# teemsyUp.net
KiCad netlist of a schematic drawn in EAGLE
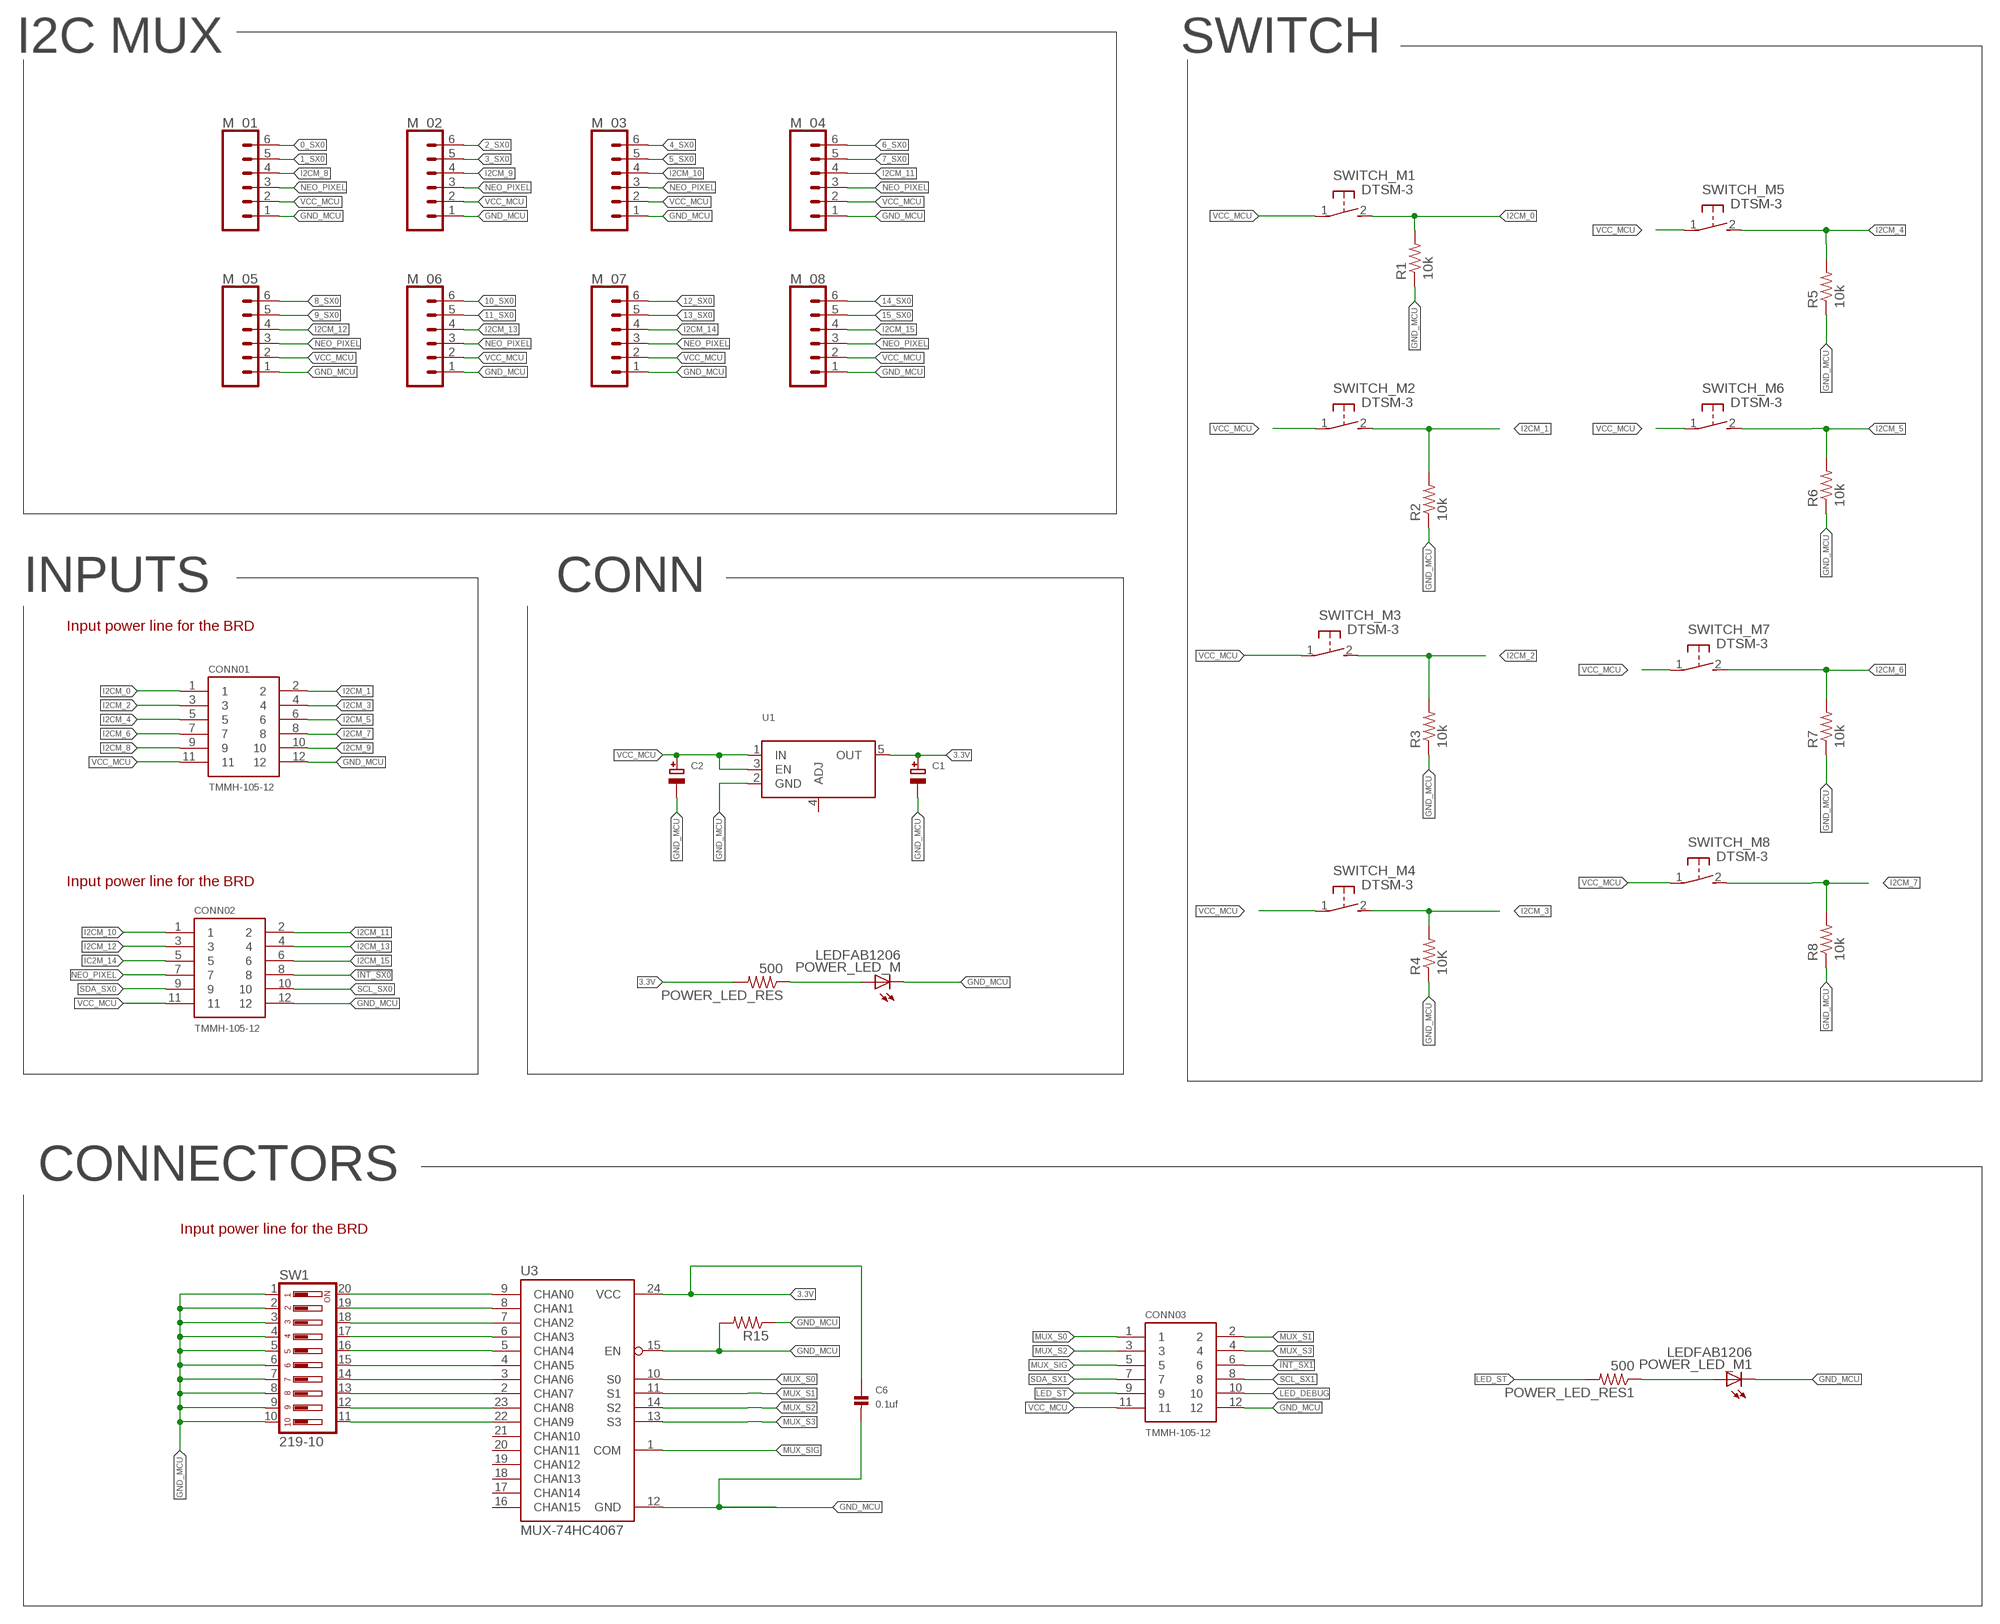
[diagram p0: schematic, sheet 1, part 1 of 2]
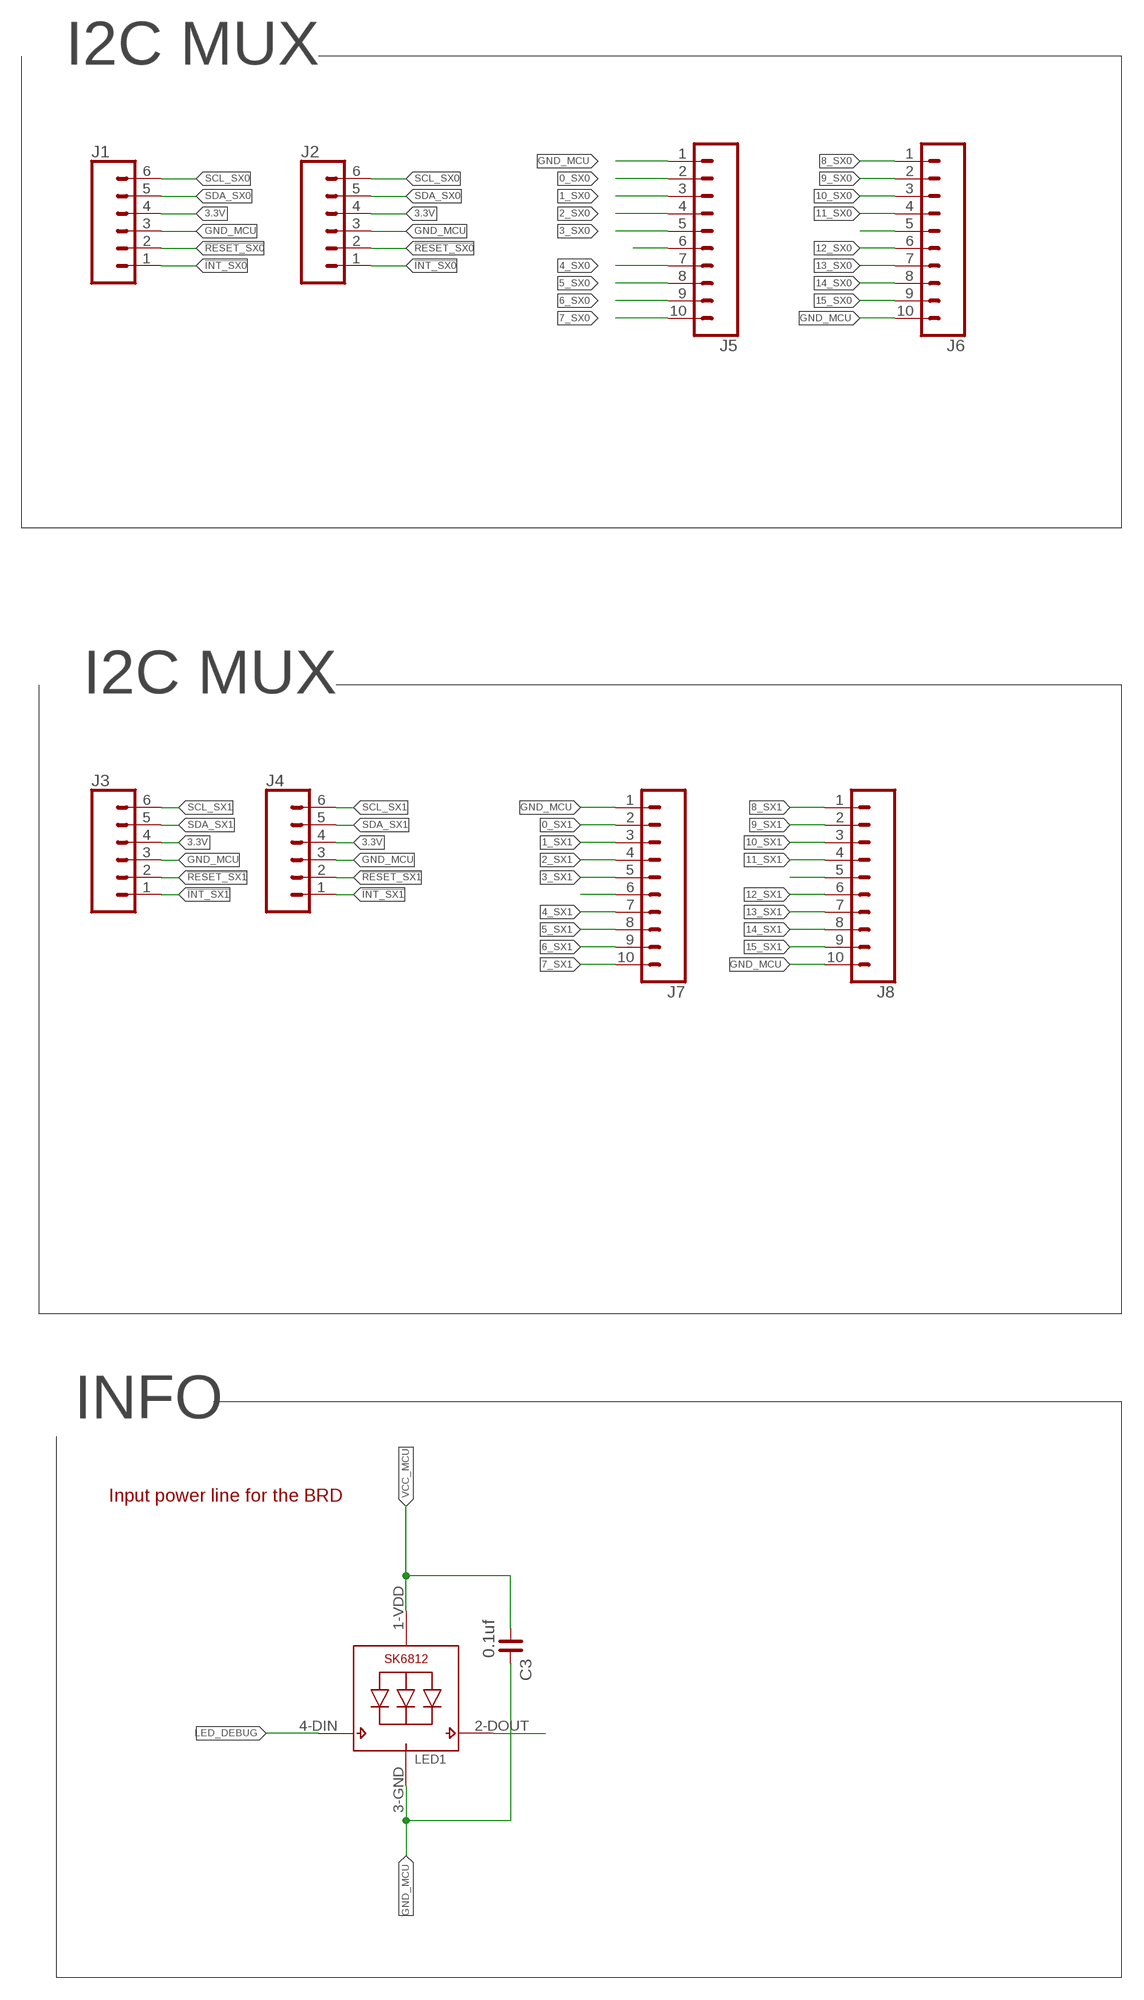
[diagram p1: schematic, sheet 1, part 2 of 2]

(export (version "E")
  (design (tool "Eeschema 10.0.6"))
  (components
    (comp (ref "C1")
      (value "CAP_TANTALUMA/3216_REFLOW")
      (footprint "eagle-import:EIA3216-18_A-R")
      (libsource (lib "eagle-import") (part "CAP_TANTALUMA/3216_REFLOW"))
    )
    (comp (ref "C2")
      (value "CAP_TANTALUMA/3216_REFLOW")
      (footprint "eagle-import:EIA3216-18_A-R")
      (libsource (lib "eagle-import") (part "CAP_TANTALUMA/3216_REFLOW"))
    )
    (comp (ref "C3")
      (value "0.1uf")
      (footprint "eagle-import:C0805")
      (libsource (lib "eagle-import") (part "C_0805"))
    )
    (comp (ref "C6")
      (value "0.1uf")
      (footprint "eagle-import:0805")
      (libsource (lib "eagle-import") (part "CAP_CERAMIC0805"))
    )
    (comp (ref "CONN01")
      (value "TMMH-105-12")
      (footprint "eagle-import:TMMH-105-12")
      (libsource (lib "eagle-import") (part "TMMH-105-12"))
    )
    (comp (ref "CONN02")
      (value "TMMH-105-12")
      (footprint "eagle-import:TMMH-105-12")
      (libsource (lib "eagle-import") (part "TMMH-105-12"))
    )
    (comp (ref "CONN03")
      (value "TMMH-105-12")
      (footprint "eagle-import:TMMH-105-12")
      (libsource (lib "eagle-import") (part "TMMH-105-12"))
    )
    (comp (ref "J1")
      (value "CONN_06SMD_MALE")
      (footprint "eagle-import:1X06_SMD_MALE")
      (libsource (lib "eagle-import") (part "CONN_06SMD_MALE"))
    )
    (comp (ref "J2")
      (value "CONN_06SMD_MALE")
      (footprint "eagle-import:1X06_SMD_MALE")
      (libsource (lib "eagle-import") (part "CONN_06SMD_MALE"))
    )
    (comp (ref "J3")
      (value "CONN_06SMD_MALE")
      (footprint "eagle-import:1X06_SMD_MALE")
      (libsource (lib "eagle-import") (part "CONN_06SMD_MALE"))
    )
    (comp (ref "J4")
      (value "CONN_06SMD_MALE")
      (footprint "eagle-import:1X06_SMD_MALE")
      (libsource (lib "eagle-import") (part "CONN_06SMD_MALE"))
    )
    (comp (ref "J5")
      (value "CONN_10SMD_MALE")
      (footprint "eagle-import:1X10_SMD_MALE")
      (libsource (lib "eagle-import") (part "CONN_10SMD_MALE"))
    )
    (comp (ref "J6")
      (value "CONN_10SMD_MALE")
      (footprint "eagle-import:1X10_SMD_MALE")
      (libsource (lib "eagle-import") (part "CONN_10SMD_MALE"))
    )
    (comp (ref "J7")
      (value "CONN_10SMD_MALE")
      (footprint "eagle-import:1X10_SMD_MALE")
      (libsource (lib "eagle-import") (part "CONN_10SMD_MALE"))
    )
    (comp (ref "J8")
      (value "CONN_10SMD_MALE")
      (footprint "eagle-import:1X10_SMD_MALE")
      (libsource (lib "eagle-import") (part "CONN_10SMD_MALE"))
    )
    (comp (ref "LED1")
      (value "SK6812_5050N")
      (footprint "eagle-import:LED5050_N")
      (libsource (lib "eagle-import") (part "SK6812_5050N"))
    )
    (comp (ref "M_01")
      (value "CONN_06SMD-1MM")
      (footprint "eagle-import:1X06-1MM")
      (libsource (lib "eagle-import") (part "CONN_06SMD-1MM"))
    )
    (comp (ref "M_02")
      (value "CONN_06SMD-1MM")
      (footprint "eagle-import:1X06-1MM")
      (libsource (lib "eagle-import") (part "CONN_06SMD-1MM"))
    )
    (comp (ref "M_03")
      (value "CONN_06SMD-1MM")
      (footprint "eagle-import:1X06-1MM")
      (libsource (lib "eagle-import") (part "CONN_06SMD-1MM"))
    )
    (comp (ref "M_04")
      (value "CONN_06SMD-1MM")
      (footprint "eagle-import:1X06-1MM")
      (libsource (lib "eagle-import") (part "CONN_06SMD-1MM"))
    )
    (comp (ref "M_05")
      (value "CONN_06SMD-1MM")
      (footprint "eagle-import:1X06-1MM")
      (libsource (lib "eagle-import") (part "CONN_06SMD-1MM"))
    )
    (comp (ref "M_06")
      (value "CONN_06SMD-1MM")
      (footprint "eagle-import:1X06-1MM")
      (libsource (lib "eagle-import") (part "CONN_06SMD-1MM"))
    )
    (comp (ref "M_07")
      (value "CONN_06SMD-1MM")
      (footprint "eagle-import:1X06-1MM")
      (libsource (lib "eagle-import") (part "CONN_06SMD-1MM"))
    )
    (comp (ref "M_08")
      (value "CONN_06SMD-1MM")
      (footprint "eagle-import:1X06-1MM")
      (libsource (lib "eagle-import") (part "CONN_06SMD-1MM"))
    )
    (comp (ref "POWER_LED_M")
      (value "LEDFAB1206")
      (footprint "eagle-import:LED1206FAB")
      (libsource (lib "eagle-import") (part "LEDFAB1206"))
    )
    (comp (ref "POWER_LED_M1")
      (value "LEDFAB1206")
      (footprint "eagle-import:LED1206FAB")
      (libsource (lib "eagle-import") (part "LEDFAB1206"))
    )
    (comp (ref "POWER_LED_RES")
      (value "500")
      (footprint "eagle-import:M0805")
      (libsource (lib "eagle-import") (part "R-US_M0805"))
    )
    (comp (ref "POWER_LED_RES1")
      (value "500")
      (footprint "eagle-import:R0805")
      (libsource (lib "eagle-import") (part "R-US_R0805"))
    )
    (comp (ref "R1")
      (value "10k")
      (footprint "eagle-import:M0805")
      (libsource (lib "eagle-import") (part "R-US_M0805"))
    )
    (comp (ref "R2")
      (value "10k")
      (footprint "eagle-import:M0805")
      (libsource (lib "eagle-import") (part "R-US_M0805"))
    )
    (comp (ref "R3")
      (value "10k")
      (footprint "eagle-import:M0805")
      (libsource (lib "eagle-import") (part "R-US_M0805"))
    )
    (comp (ref "R4")
      (value "10K")
      (footprint "eagle-import:M0805")
      (libsource (lib "eagle-import") (part "R-US_M0805"))
    )
    (comp (ref "R5")
      (value "10k")
      (footprint "eagle-import:M0805")
      (libsource (lib "eagle-import") (part "R-US_M0805"))
    )
    (comp (ref "R6")
      (value "10k")
      (footprint "eagle-import:M0805")
      (libsource (lib "eagle-import") (part "R-US_M0805"))
    )
    (comp (ref "R7")
      (value "10k")
      (footprint "eagle-import:M0805")
      (libsource (lib "eagle-import") (part "R-US_M0805"))
    )
    (comp (ref "R8")
      (value "10k")
      (footprint "eagle-import:M0805")
      (libsource (lib "eagle-import") (part "R-US_M0805"))
    )
    (comp (ref "R15")
      (value "R-US_M0805")
      (footprint "eagle-import:M0805")
      (libsource (lib "eagle-import") (part "R-US_M0805"))
    )
    (comp (ref "SW1")
      (value "219-10")
      (footprint "eagle-import:CTS-219-10")
      (fields (field (name "MF") "SLI (CML/IDI)") (field (name "MPN") "219-10PK"))
      (libsource (lib "eagle-import") (part "219-10"))
    )
    (comp (ref "SWITCH_M1")
      (value "DTSM-3")
      (footprint "eagle-import:DTSM-3")
      (libsource (lib "eagle-import") (part "DTSM-3"))
    )
    (comp (ref "SWITCH_M2")
      (value "DTSM-3")
      (footprint "eagle-import:DTSM-3")
      (libsource (lib "eagle-import") (part "DTSM-3"))
    )
    (comp (ref "SWITCH_M3")
      (value "DTSM-3")
      (footprint "eagle-import:DTSM-3")
      (libsource (lib "eagle-import") (part "DTSM-3"))
    )
    (comp (ref "SWITCH_M4")
      (value "DTSM-3")
      (footprint "eagle-import:DTSM-3")
      (libsource (lib "eagle-import") (part "DTSM-3"))
    )
    (comp (ref "SWITCH_M5")
      (value "DTSM-3")
      (footprint "eagle-import:DTSM-3")
      (libsource (lib "eagle-import") (part "DTSM-3"))
    )
    (comp (ref "SWITCH_M6")
      (value "DTSM-3")
      (footprint "eagle-import:DTSM-3")
      (libsource (lib "eagle-import") (part "DTSM-3"))
    )
    (comp (ref "SWITCH_M7")
      (value "DTSM-3")
      (footprint "eagle-import:DTSM-3")
      (libsource (lib "eagle-import") (part "DTSM-3"))
    )
    (comp (ref "SWITCH_M8")
      (value "DTSM-3")
      (footprint "eagle-import:DTSM-3")
      (libsource (lib "eagle-import") (part "DTSM-3"))
    )
    (comp (ref "U1")
      (value "ADP1712")
      (footprint "eagle-import:SOT23-5")
      (libsource (lib "eagle-import") (part "ADP1712"))
    )
    (comp (ref "U3")
      (value "MUX-74HC4067")
      (footprint "eagle-import:SSOP24")
      (libsource (lib "eagle-import") (part "MUX-74HC4067SMD"))
    )
  )
  (nets
    (net (code "1") (name "/~{INT_SX0}") (class "Default")
      (node (ref "CONN02") (pin "8") (pinfunction "8_8") (pintype "bidirectional"))
      (node (ref "J1") (pin "1") (pinfunction "1_1") (pintype "passive"))
      (node (ref "J2") (pin "1") (pinfunction "1_1") (pintype "passive"))
    )
    (net (code "2") (name "/~{INT_SX1}") (class "Default")
      (node (ref "CONN03") (pin "6") (pinfunction "6_6") (pintype "bidirectional"))
      (node (ref "J3") (pin "1") (pinfunction "1_1") (pintype "passive"))
      (node (ref "J4") (pin "1") (pinfunction "1_1") (pintype "passive"))
    )
    (net (code "3") (name "/~{RESET_SX0}") (class "Default")
      (node (ref "J1") (pin "2") (pinfunction "2_2") (pintype "passive"))
      (node (ref "J2") (pin "2") (pinfunction "2_2") (pintype "passive"))
    )
    (net (code "4") (name "/~{RESET_SX1}") (class "Default")
      (node (ref "J3") (pin "2") (pinfunction "2_2") (pintype "passive"))
      (node (ref "J4") (pin "2") (pinfunction "2_2") (pintype "passive"))
    )
    (net (code "5") (name "0_SX0") (class "Default")
      (node (ref "J5") (pin "2") (pinfunction "2_2") (pintype "passive"))
      (node (ref "M_01") (pin "6") (pinfunction "6_6") (pintype "passive"))
    )
    (net (code "6") (name "0_SX1") (class "Default")
      (node (ref "J7") (pin "2") (pinfunction "2_2") (pintype "passive"))
    )
    (net (code "7") (name "1_SX0") (class "Default")
      (node (ref "J5") (pin "3") (pinfunction "3_3") (pintype "passive"))
      (node (ref "M_01") (pin "5") (pinfunction "5_5") (pintype "passive"))
    )
    (net (code "8") (name "1_SX1") (class "Default")
      (node (ref "J7") (pin "3") (pinfunction "3_3") (pintype "passive"))
    )
    (net (code "9") (name "2_SX0") (class "Default")
      (node (ref "J5") (pin "4") (pinfunction "4_4") (pintype "passive"))
      (node (ref "M_02") (pin "6") (pinfunction "6_6") (pintype "passive"))
    )
    (net (code "10") (name "2_SX1") (class "Default")
      (node (ref "J7") (pin "4") (pinfunction "4_4") (pintype "passive"))
    )
    (net (code "11") (name "3.3V") (class "Default")
      (node (ref "C1") (pin "+") (pinfunction "+_+") (pintype "passive"))
      (node (ref "C6") (pin "1") (pinfunction "P$1_1") (pintype "passive"))
      (node (ref "J1") (pin "4") (pinfunction "4_4") (pintype "passive"))
      (node (ref "J2") (pin "4") (pinfunction "4_4") (pintype "passive"))
      (node (ref "J3") (pin "4") (pinfunction "4_4") (pintype "passive"))
      (node (ref "J4") (pin "4") (pinfunction "4_4") (pintype "passive"))
      (node (ref "POWER_LED_RES") (pin "2") (pinfunction "2_2") (pintype "passive"))
      (node (ref "U1") (pin "5") (pinfunction "OUT_5") (pintype "bidirectional"))
      (node (ref "U3") (pin "24") (pinfunction "VCC_24") (pintype "bidirectional"))
    )
    (net (code "12") (name "3_SX0") (class "Default")
      (node (ref "J5") (pin "5") (pinfunction "5_5") (pintype "passive"))
      (node (ref "M_02") (pin "5") (pinfunction "5_5") (pintype "passive"))
    )
    (net (code "13") (name "3_SX1") (class "Default")
      (node (ref "J7") (pin "5") (pinfunction "5_5") (pintype "passive"))
    )
    (net (code "14") (name "4_SX0") (class "Default")
      (node (ref "J5") (pin "7") (pinfunction "7_7") (pintype "passive"))
      (node (ref "M_03") (pin "6") (pinfunction "6_6") (pintype "passive"))
    )
    (net (code "15") (name "4_SX1") (class "Default")
      (node (ref "J7") (pin "7") (pinfunction "7_7") (pintype "passive"))
    )
    (net (code "16") (name "5_SX0") (class "Default")
      (node (ref "J5") (pin "8") (pinfunction "8_8") (pintype "passive"))
      (node (ref "M_03") (pin "5") (pinfunction "5_5") (pintype "passive"))
    )
    (net (code "17") (name "5_SX1") (class "Default")
      (node (ref "J7") (pin "8") (pinfunction "8_8") (pintype "passive"))
    )
    (net (code "18") (name "6_SX0") (class "Default")
      (node (ref "J5") (pin "9") (pinfunction "9_9") (pintype "passive"))
      (node (ref "M_04") (pin "6") (pinfunction "6_6") (pintype "passive"))
    )
    (net (code "19") (name "6_SX1") (class "Default")
      (node (ref "J7") (pin "9") (pinfunction "9_9") (pintype "passive"))
    )
    (net (code "20") (name "7_SX0") (class "Default")
      (node (ref "J5") (pin "10") (pinfunction "10_10") (pintype "passive"))
      (node (ref "M_04") (pin "5") (pinfunction "5_5") (pintype "passive"))
    )
    (net (code "21") (name "7_SX1") (class "Default")
      (node (ref "J7") (pin "10") (pinfunction "10_10") (pintype "passive"))
    )
    (net (code "22") (name "8_SX0") (class "Default")
      (node (ref "J6") (pin "1") (pinfunction "1_1") (pintype "passive"))
      (node (ref "M_05") (pin "6") (pinfunction "6_6") (pintype "passive"))
    )
    (net (code "23") (name "8_SX1") (class "Default")
      (node (ref "J8") (pin "1") (pinfunction "1_1") (pintype "passive"))
    )
    (net (code "24") (name "9_SX0") (class "Default")
      (node (ref "J6") (pin "2") (pinfunction "2_2") (pintype "passive"))
      (node (ref "M_05") (pin "5") (pinfunction "5_5") (pintype "passive"))
    )
    (net (code "25") (name "9_SX1") (class "Default")
      (node (ref "J8") (pin "2") (pinfunction "2_2") (pintype "passive"))
    )
    (net (code "26") (name "10_SX0") (class "Default")
      (node (ref "J6") (pin "3") (pinfunction "3_3") (pintype "passive"))
      (node (ref "M_06") (pin "6") (pinfunction "6_6") (pintype "passive"))
    )
    (net (code "27") (name "10_SX1") (class "Default")
      (node (ref "J8") (pin "3") (pinfunction "3_3") (pintype "passive"))
    )
    (net (code "28") (name "11_SX0") (class "Default")
      (node (ref "J6") (pin "4") (pinfunction "4_4") (pintype "passive"))
      (node (ref "M_06") (pin "5") (pinfunction "5_5") (pintype "passive"))
    )
    (net (code "29") (name "11_SX1") (class "Default")
      (node (ref "J8") (pin "4") (pinfunction "4_4") (pintype "passive"))
    )
    (net (code "30") (name "12_SX0") (class "Default")
      (node (ref "J6") (pin "6") (pinfunction "6_6") (pintype "passive"))
      (node (ref "M_07") (pin "6") (pinfunction "6_6") (pintype "passive"))
    )
    (net (code "31") (name "12_SX1") (class "Default")
      (node (ref "J8") (pin "6") (pinfunction "6_6") (pintype "passive"))
    )
    (net (code "32") (name "13_SX0") (class "Default")
      (node (ref "J6") (pin "7") (pinfunction "7_7") (pintype "passive"))
      (node (ref "M_07") (pin "5") (pinfunction "5_5") (pintype "passive"))
    )
    (net (code "33") (name "13_SX1") (class "Default")
      (node (ref "J8") (pin "7") (pinfunction "7_7") (pintype "passive"))
    )
    (net (code "34") (name "14_SX0") (class "Default")
      (node (ref "J6") (pin "8") (pinfunction "8_8") (pintype "passive"))
      (node (ref "M_08") (pin "6") (pinfunction "6_6") (pintype "passive"))
    )
    (net (code "35") (name "14_SX1") (class "Default")
      (node (ref "J8") (pin "8") (pinfunction "8_8") (pintype "passive"))
    )
    (net (code "36") (name "15_SX0") (class "Default")
      (node (ref "J6") (pin "9") (pinfunction "9_9") (pintype "passive"))
      (node (ref "M_08") (pin "5") (pinfunction "5_5") (pintype "passive"))
    )
    (net (code "37") (name "15_SX1") (class "Default")
      (node (ref "J8") (pin "9") (pinfunction "9_9") (pintype "passive"))
    )
    (net (code "38") (name "GND_MCU") (class "Default")
      (node (ref "C1") (pin "-") (pinfunction "-_-") (pintype "passive"))
      (node (ref "C2") (pin "-") (pinfunction "-_-") (pintype "passive"))
      (node (ref "C3") (pin "2") (pinfunction "2_2") (pintype "passive"))
      (node (ref "C6") (pin "2") (pinfunction "P$2_2") (pintype "passive"))
      (node (ref "CONN01") (pin "12") (pinfunction "12_12") (pintype "bidirectional"))
      (node (ref "CONN02") (pin "12") (pinfunction "12_12") (pintype "bidirectional"))
      (node (ref "CONN03") (pin "12") (pinfunction "12_12") (pintype "bidirectional"))
      (node (ref "J1") (pin "3") (pinfunction "3_3") (pintype "passive"))
      (node (ref "J2") (pin "3") (pinfunction "3_3") (pintype "passive"))
      (node (ref "J3") (pin "3") (pinfunction "3_3") (pintype "passive"))
      (node (ref "J4") (pin "3") (pinfunction "3_3") (pintype "passive"))
      (node (ref "J5") (pin "1") (pinfunction "1_1") (pintype "passive"))
      (node (ref "J6") (pin "10") (pinfunction "10_10") (pintype "passive"))
      (node (ref "J7") (pin "1") (pinfunction "1_1") (pintype "passive"))
      (node (ref "J8") (pin "10") (pinfunction "10_10") (pintype "passive"))
      (node (ref "LED1") (pin "3-GND") (pinfunction "GND_3-GND") (pintype "power_in"))
      (node (ref "M_01") (pin "1") (pinfunction "1_1") (pintype "passive"))
      (node (ref "M_02") (pin "1") (pinfunction "1_1") (pintype "passive"))
      (node (ref "M_03") (pin "1") (pinfunction "1_1") (pintype "passive"))
      (node (ref "M_04") (pin "1") (pinfunction "1_1") (pintype "passive"))
      (node (ref "M_05") (pin "1") (pinfunction "1_1") (pintype "passive"))
      (node (ref "M_06") (pin "1") (pinfunction "1_1") (pintype "passive"))
      (node (ref "M_07") (pin "1") (pinfunction "1_1") (pintype "passive"))
      (node (ref "M_08") (pin "1") (pinfunction "1_1") (pintype "passive"))
      (node (ref "POWER_LED_M") (pin "2") (pinfunction "C_2") (pintype "passive"))
      (node (ref "POWER_LED_M1") (pin "2") (pinfunction "C_2") (pintype "passive"))
      (node (ref "R1") (pin "1") (pinfunction "1_1") (pintype "passive"))
      (node (ref "R15") (pin "1") (pinfunction "1_1") (pintype "passive"))
      (node (ref "R15") (pin "2") (pinfunction "2_2") (pintype "passive"))
      (node (ref "R2") (pin "1") (pinfunction "1_1") (pintype "passive"))
      (node (ref "R3") (pin "1") (pinfunction "1_1") (pintype "passive"))
      (node (ref "R4") (pin "1") (pinfunction "1_1") (pintype "passive"))
      (node (ref "R5") (pin "1") (pinfunction "1_1") (pintype "passive"))
      (node (ref "R6") (pin "1") (pinfunction "1_1") (pintype "passive"))
      (node (ref "R7") (pin "1") (pinfunction "1_1") (pintype "passive"))
      (node (ref "R8") (pin "1") (pinfunction "1_1") (pintype "passive"))
      (node (ref "SW1") (pin "1") (pinfunction "1_1") (pintype "passive"))
      (node (ref "SW1") (pin "10") (pinfunction "10_10") (pintype "passive"))
      (node (ref "SW1") (pin "2") (pinfunction "2_2") (pintype "passive"))
      (node (ref "SW1") (pin "3") (pinfunction "3_3") (pintype "passive"))
      (node (ref "SW1") (pin "4") (pinfunction "4_4") (pintype "passive"))
      (node (ref "SW1") (pin "5") (pinfunction "5_5") (pintype "passive"))
      (node (ref "SW1") (pin "6") (pinfunction "6_6") (pintype "passive"))
      (node (ref "SW1") (pin "7") (pinfunction "7_7") (pintype "passive"))
      (node (ref "SW1") (pin "8") (pinfunction "8_8") (pintype "passive"))
      (node (ref "SW1") (pin "9") (pinfunction "9_9") (pintype "passive"))
      (node (ref "U1") (pin "2") (pinfunction "GND_2") (pintype "bidirectional"))
      (node (ref "U3") (pin "12") (pinfunction "GND_12") (pintype "bidirectional"))
      (node (ref "U3") (pin "15") (pinfunction "EN_15") (pintype "input"))
    )
    (net (code "39") (name "I2CM_0") (class "Default")
      (node (ref "CONN01") (pin "1") (pinfunction "1_1") (pintype "bidirectional"))
      (node (ref "R1") (pin "2") (pinfunction "2_2") (pintype "passive"))
      (node (ref "SWITCH_M1") (pin "2") (pinfunction "2_2") (pintype "passive"))
    )
    (net (code "40") (name "I2CM_1") (class "Default")
      (node (ref "CONN01") (pin "2") (pinfunction "2_2") (pintype "bidirectional"))
      (node (ref "R2") (pin "2") (pinfunction "2_2") (pintype "passive"))
      (node (ref "SWITCH_M2") (pin "2") (pinfunction "2_2") (pintype "passive"))
    )
    (net (code "41") (name "I2CM_2") (class "Default")
      (node (ref "CONN01") (pin "3") (pinfunction "3_3") (pintype "bidirectional"))
      (node (ref "R3") (pin "2") (pinfunction "2_2") (pintype "passive"))
      (node (ref "SWITCH_M3") (pin "2") (pinfunction "2_2") (pintype "passive"))
    )
    (net (code "42") (name "I2CM_3") (class "Default")
      (node (ref "CONN01") (pin "4") (pinfunction "4_4") (pintype "bidirectional"))
      (node (ref "R4") (pin "2") (pinfunction "2_2") (pintype "passive"))
      (node (ref "SWITCH_M4") (pin "2") (pinfunction "2_2") (pintype "passive"))
    )
    (net (code "43") (name "I2CM_4") (class "Default")
      (node (ref "CONN01") (pin "5") (pinfunction "5_5") (pintype "bidirectional"))
      (node (ref "R5") (pin "2") (pinfunction "2_2") (pintype "passive"))
      (node (ref "SWITCH_M5") (pin "2") (pinfunction "2_2") (pintype "passive"))
    )
    (net (code "44") (name "I2CM_5") (class "Default")
      (node (ref "CONN01") (pin "6") (pinfunction "6_6") (pintype "bidirectional"))
      (node (ref "R6") (pin "2") (pinfunction "2_2") (pintype "passive"))
      (node (ref "SWITCH_M6") (pin "2") (pinfunction "2_2") (pintype "passive"))
    )
    (net (code "45") (name "I2CM_6") (class "Default")
      (node (ref "CONN01") (pin "7") (pinfunction "7_7") (pintype "bidirectional"))
      (node (ref "R7") (pin "2") (pinfunction "2_2") (pintype "passive"))
      (node (ref "SWITCH_M7") (pin "2") (pinfunction "2_2") (pintype "passive"))
    )
    (net (code "46") (name "I2CM_7") (class "Default")
      (node (ref "CONN01") (pin "8") (pinfunction "8_8") (pintype "bidirectional"))
      (node (ref "R8") (pin "2") (pinfunction "2_2") (pintype "passive"))
      (node (ref "SWITCH_M8") (pin "2") (pinfunction "2_2") (pintype "passive"))
    )
    (net (code "47") (name "I2CM_8") (class "Default")
      (node (ref "CONN01") (pin "9") (pinfunction "9_9") (pintype "bidirectional"))
      (node (ref "M_01") (pin "4") (pinfunction "4_4") (pintype "passive"))
    )
    (net (code "48") (name "I2CM_9") (class "Default")
      (node (ref "CONN01") (pin "10") (pinfunction "10_10") (pintype "bidirectional"))
      (node (ref "M_02") (pin "4") (pinfunction "4_4") (pintype "passive"))
    )
    (net (code "49") (name "I2CM_10") (class "Default")
      (node (ref "CONN02") (pin "1") (pinfunction "1_1") (pintype "bidirectional"))
      (node (ref "M_03") (pin "4") (pinfunction "4_4") (pintype "passive"))
    )
    (net (code "50") (name "I2CM_11") (class "Default")
      (node (ref "CONN02") (pin "2") (pinfunction "2_2") (pintype "bidirectional"))
      (node (ref "M_04") (pin "4") (pinfunction "4_4") (pintype "passive"))
    )
    (net (code "51") (name "I2CM_12") (class "Default")
      (node (ref "CONN02") (pin "3") (pinfunction "3_3") (pintype "bidirectional"))
      (node (ref "M_05") (pin "4") (pinfunction "4_4") (pintype "passive"))
    )
    (net (code "52") (name "I2CM_13") (class "Default")
      (node (ref "CONN02") (pin "4") (pinfunction "4_4") (pintype "bidirectional"))
      (node (ref "M_06") (pin "4") (pinfunction "4_4") (pintype "passive"))
    )
    (net (code "53") (name "I2CM_14") (class "Default")
      (node (ref "M_07") (pin "4") (pinfunction "4_4") (pintype "passive"))
    )
    (net (code "54") (name "I2CM_15") (class "Default")
      (node (ref "CONN02") (pin "6") (pinfunction "6_6") (pintype "bidirectional"))
      (node (ref "M_08") (pin "4") (pinfunction "4_4") (pintype "passive"))
    )
    (net (code "55") (name "IC2M_14") (class "Default")
      (node (ref "CONN02") (pin "5") (pinfunction "5_5") (pintype "bidirectional"))
    )
    (net (code "56") (name "LED_DEBUG") (class "Default")
      (node (ref "CONN03") (pin "10") (pinfunction "10_10") (pintype "bidirectional"))
      (node (ref "LED1") (pin "4-DIN") (pinfunction "DI_4-DIN") (pintype "input"))
    )
    (net (code "57") (name "LED_ST") (class "Default")
      (node (ref "CONN03") (pin "9") (pinfunction "9_9") (pintype "bidirectional"))
      (node (ref "POWER_LED_RES1") (pin "2") (pinfunction "2_2") (pintype "passive"))
    )
    (net (code "58") (name "MUX_S0") (class "Default")
      (node (ref "CONN03") (pin "1") (pinfunction "1_1") (pintype "bidirectional"))
      (node (ref "U3") (pin "10") (pinfunction "S0_10") (pintype "input"))
    )
    (net (code "59") (name "MUX_S1") (class "Default")
      (node (ref "CONN03") (pin "2") (pinfunction "2_2") (pintype "bidirectional"))
      (node (ref "U3") (pin "11") (pinfunction "S1_11") (pintype "input"))
    )
    (net (code "60") (name "MUX_S2") (class "Default")
      (node (ref "CONN03") (pin "3") (pinfunction "3_3") (pintype "bidirectional"))
      (node (ref "U3") (pin "14") (pinfunction "S2_14") (pintype "input"))
    )
    (net (code "61") (name "MUX_S3") (class "Default")
      (node (ref "CONN03") (pin "4") (pinfunction "4_4") (pintype "bidirectional"))
      (node (ref "U3") (pin "13") (pinfunction "S3_13") (pintype "input"))
    )
    (net (code "62") (name "MUX_SIG") (class "Default")
      (node (ref "CONN03") (pin "5") (pinfunction "5_5") (pintype "bidirectional"))
      (node (ref "U3") (pin "1") (pinfunction "COM_1") (pintype "bidirectional"))
    )
    (net (code "63") (name "NEO_PIXEL") (class "Default")
      (node (ref "CONN02") (pin "7") (pinfunction "7_7") (pintype "bidirectional"))
      (node (ref "M_01") (pin "3") (pinfunction "3_3") (pintype "passive"))
      (node (ref "M_02") (pin "3") (pinfunction "3_3") (pintype "passive"))
      (node (ref "M_03") (pin "3") (pinfunction "3_3") (pintype "passive"))
      (node (ref "M_04") (pin "3") (pinfunction "3_3") (pintype "passive"))
      (node (ref "M_05") (pin "3") (pinfunction "3_3") (pintype "passive"))
      (node (ref "M_06") (pin "3") (pinfunction "3_3") (pintype "passive"))
      (node (ref "M_07") (pin "3") (pinfunction "3_3") (pintype "passive"))
      (node (ref "M_08") (pin "3") (pinfunction "3_3") (pintype "passive"))
    )
    (net (code "64") (name "Net-(POWER_LED_M-A)") (class "Default")
      (node (ref "POWER_LED_M") (pin "1") (pinfunction "A_1") (pintype "passive"))
      (node (ref "POWER_LED_RES") (pin "1") (pinfunction "1_1") (pintype "passive"))
    )
    (net (code "65") (name "Net-(POWER_LED_M1-A)") (class "Default")
      (node (ref "POWER_LED_M1") (pin "1") (pinfunction "A_1") (pintype "passive"))
      (node (ref "POWER_LED_RES1") (pin "1") (pinfunction "1_1") (pintype "passive"))
    )
    (net (code "66") (name "Net-(U3-CHAN0)") (class "Default")
      (node (ref "SW1") (pin "20") (pinfunction "20_20") (pintype "passive"))
      (node (ref "U3") (pin "9") (pinfunction "CHAN0_9") (pintype "bidirectional"))
    )
    (net (code "67") (name "Net-(U3-CHAN1)") (class "Default")
      (node (ref "SW1") (pin "19") (pinfunction "19_19") (pintype "passive"))
      (node (ref "U3") (pin "8") (pinfunction "CHAN1_8") (pintype "bidirectional"))
    )
    (net (code "68") (name "Net-(U3-CHAN2)") (class "Default")
      (node (ref "SW1") (pin "18") (pinfunction "18_18") (pintype "passive"))
      (node (ref "U3") (pin "7") (pinfunction "CHAN2_7") (pintype "bidirectional"))
    )
    (net (code "69") (name "Net-(U3-CHAN3)") (class "Default")
      (node (ref "SW1") (pin "17") (pinfunction "17_17") (pintype "passive"))
      (node (ref "U3") (pin "6") (pinfunction "CHAN3_6") (pintype "bidirectional"))
    )
    (net (code "70") (name "Net-(U3-CHAN4)") (class "Default")
      (node (ref "SW1") (pin "16") (pinfunction "16_16") (pintype "passive"))
      (node (ref "U3") (pin "5") (pinfunction "CHAN4_5") (pintype "bidirectional"))
    )
    (net (code "71") (name "Net-(U3-CHAN5)") (class "Default")
      (node (ref "SW1") (pin "15") (pinfunction "15_15") (pintype "passive"))
      (node (ref "U3") (pin "4") (pinfunction "CHAN5_4") (pintype "bidirectional"))
    )
    (net (code "72") (name "Net-(U3-CHAN6)") (class "Default")
      (node (ref "SW1") (pin "14") (pinfunction "14_14") (pintype "passive"))
      (node (ref "U3") (pin "3") (pinfunction "CHAN6_3") (pintype "bidirectional"))
    )
    (net (code "73") (name "Net-(U3-CHAN7)") (class "Default")
      (node (ref "SW1") (pin "13") (pinfunction "13_13") (pintype "passive"))
      (node (ref "U3") (pin "2") (pinfunction "CHAN7_2") (pintype "bidirectional"))
    )
    (net (code "74") (name "Net-(U3-CHAN8)") (class "Default")
      (node (ref "SW1") (pin "12") (pinfunction "12_12") (pintype "passive"))
      (node (ref "U3") (pin "23") (pinfunction "CHAN8_23") (pintype "bidirectional"))
    )
    (net (code "75") (name "Net-(U3-CHAN9)") (class "Default")
      (node (ref "SW1") (pin "11") (pinfunction "11_11") (pintype "passive"))
      (node (ref "U3") (pin "22") (pinfunction "CHAN9_22") (pintype "bidirectional"))
    )
    (net (code "76") (name "SCL_SX0") (class "Default")
      (node (ref "CONN02") (pin "10") (pinfunction "10_10") (pintype "bidirectional"))
      (node (ref "J1") (pin "6") (pinfunction "6_6") (pintype "passive"))
      (node (ref "J2") (pin "6") (pinfunction "6_6") (pintype "passive"))
    )
    (net (code "77") (name "SCL_SX1") (class "Default")
      (node (ref "CONN03") (pin "8") (pinfunction "8_8") (pintype "bidirectional"))
      (node (ref "J3") (pin "6") (pinfunction "6_6") (pintype "passive"))
      (node (ref "J4") (pin "6") (pinfunction "6_6") (pintype "passive"))
    )
    (net (code "78") (name "SDA_SX0") (class "Default")
      (node (ref "CONN02") (pin "9") (pinfunction "9_9") (pintype "bidirectional"))
      (node (ref "J1") (pin "5") (pinfunction "5_5") (pintype "passive"))
      (node (ref "J2") (pin "5") (pinfunction "5_5") (pintype "passive"))
    )
    (net (code "79") (name "SDA_SX1") (class "Default")
      (node (ref "CONN03") (pin "7") (pinfunction "7_7") (pintype "bidirectional"))
      (node (ref "J3") (pin "5") (pinfunction "5_5") (pintype "passive"))
      (node (ref "J4") (pin "5") (pinfunction "5_5") (pintype "passive"))
    )
    (net (code "80") (name "VCC_MCU") (class "Default")
      (node (ref "C2") (pin "+") (pinfunction "+_+") (pintype "passive"))
      (node (ref "C3") (pin "1") (pinfunction "1_1") (pintype "passive"))
      (node (ref "CONN01") (pin "11") (pinfunction "11_11") (pintype "bidirectional"))
      (node (ref "CONN02") (pin "11") (pinfunction "11_11") (pintype "bidirectional"))
      (node (ref "CONN03") (pin "11") (pinfunction "11_11") (pintype "bidirectional"))
      (node (ref "LED1") (pin "1-VDD") (pinfunction "VDD_1-VDD") (pintype "power_in"))
      (node (ref "M_01") (pin "2") (pinfunction "2_2") (pintype "passive"))
      (node (ref "M_02") (pin "2") (pinfunction "2_2") (pintype "passive"))
      (node (ref "M_03") (pin "2") (pinfunction "2_2") (pintype "passive"))
      (node (ref "M_04") (pin "2") (pinfunction "2_2") (pintype "passive"))
      (node (ref "M_05") (pin "2") (pinfunction "2_2") (pintype "passive"))
      (node (ref "M_06") (pin "2") (pinfunction "2_2") (pintype "passive"))
      (node (ref "M_07") (pin "2") (pinfunction "2_2") (pintype "passive"))
      (node (ref "M_08") (pin "2") (pinfunction "2_2") (pintype "passive"))
      (node (ref "SWITCH_M1") (pin "1") (pinfunction "1_1") (pintype "passive"))
      (node (ref "SWITCH_M2") (pin "1") (pinfunction "1_1") (pintype "passive"))
      (node (ref "SWITCH_M3") (pin "1") (pinfunction "1_1") (pintype "passive"))
      (node (ref "SWITCH_M4") (pin "1") (pinfunction "1_1") (pintype "passive"))
      (node (ref "SWITCH_M5") (pin "1") (pinfunction "1_1") (pintype "passive"))
      (node (ref "SWITCH_M6") (pin "1") (pinfunction "1_1") (pintype "passive"))
      (node (ref "SWITCH_M7") (pin "1") (pinfunction "1_1") (pintype "passive"))
      (node (ref "SWITCH_M8") (pin "1") (pinfunction "1_1") (pintype "passive"))
      (node (ref "U1") (pin "1") (pinfunction "IN_1") (pintype "bidirectional"))
      (node (ref "U1") (pin "3") (pinfunction "EN_3") (pintype "bidirectional"))
    )
    (net (code "81") (name "unconnected-(J5-Pad6)") (class "Default")
      (node (ref "J5") (pin "6") (pinfunction "6_6") (pintype "passive"))
    )
    (net (code "82") (name "unconnected-(J6-Pad5)") (class "Default")
      (node (ref "J6") (pin "5") (pinfunction "5_5") (pintype "passive"))
    )
    (net (code "83") (name "unconnected-(J7-Pad6)") (class "Default")
      (node (ref "J7") (pin "6") (pinfunction "6_6") (pintype "passive"))
    )
    (net (code "84") (name "unconnected-(J8-Pad5)") (class "Default")
      (node (ref "J8") (pin "5") (pinfunction "5_5") (pintype "passive"))
    )
    (net (code "85") (name "unconnected-(LED1-DO-Pad2-DOUT)") (class "Default")
      (node (ref "LED1") (pin "2-DOUT") (pinfunction "DO_2-DOUT") (pintype "output"))
    )
    (net (code "86") (name "unconnected-(U1-ADJ-Pad4)") (class "Default")
      (node (ref "U1") (pin "4") (pinfunction "ADJ_4") (pintype "bidirectional"))
    )
    (net (code "87") (name "unconnected-(U3-CHAN10-Pad21)") (class "Default")
      (node (ref "U3") (pin "21") (pinfunction "CHAN10_21") (pintype "bidirectional"))
    )
    (net (code "88") (name "unconnected-(U3-CHAN11-Pad20)") (class "Default")
      (node (ref "U3") (pin "20") (pinfunction "CHAN11_20") (pintype "bidirectional"))
    )
    (net (code "89") (name "unconnected-(U3-CHAN12-Pad19)") (class "Default")
      (node (ref "U3") (pin "19") (pinfunction "CHAN12_19") (pintype "bidirectional"))
    )
    (net (code "90") (name "unconnected-(U3-CHAN13-Pad18)") (class "Default")
      (node (ref "U3") (pin "18") (pinfunction "CHAN13_18") (pintype "bidirectional"))
    )
    (net (code "91") (name "unconnected-(U3-CHAN14-Pad17)") (class "Default")
      (node (ref "U3") (pin "17") (pinfunction "CHAN14_17") (pintype "bidirectional"))
    )
    (net (code "92") (name "unconnected-(U3-CHAN15-Pad16)") (class "Default")
      (node (ref "U3") (pin "16") (pinfunction "CHAN15_16") (pintype "bidirectional"))
    )
  )
)
